# 6_RgbLed.net
KiCad netlist of a schematic drawn in Altium Designer
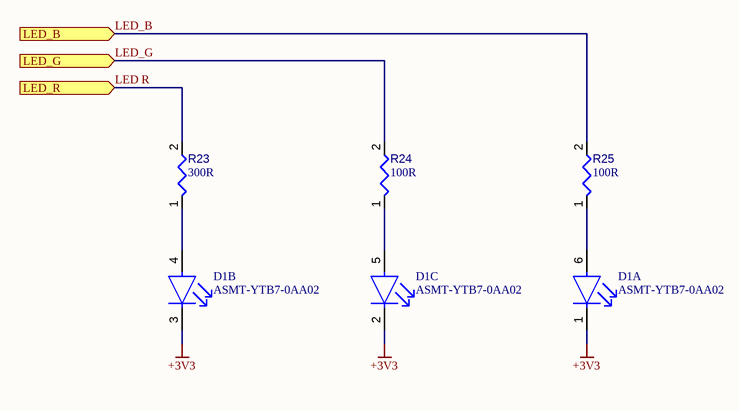
[diagram p0: [6] RgbLed.SchDoc]

(export (version "E")
  (design (tool "Eeschema 10.0.6"))
  (components
    (comp (ref "D1")
      (value "ASMT-YTB7-0AA02")
      (footprint "FP-PLCC-6-MFG")
      (description "LED Tri-Color Blue/Green/Red 469nm/529nm/623nm Chip LED 6-Pin PLCC T/R")
      (libsource (lib "UFCG - Universidade Federal de Campina Grande") (part "0f3d36aaa98356051a15b42400af8f3"))
    )
    (comp (ref "R23")
      (value "300R")
      (footprint "RESC0603(1608)_L")
      (description "Res Thick Film 0603 300 Ohm 5% 1/10W ±200ppm/°C Molded SMD Punched Carrier T/R")
      (fields (field (name "TOLERANCE") "5%") (field (name "Comment") "ERJ-3GEYJ301V"))
      (libsource (lib "UFCG - Universidade Federal de Campina Grande") (part "RES-2"))
    )
    (comp (ref "R24")
      (value "100R")
      (footprint "RESC0603(1608)_L")
      (description "SMD Chip Resistor, 100 Ohm, ï¿½ 1%, 100 mW, 0603 [1608 Metric], Thick Film, Precision")
      (fields (field (name "TOLERANCE") "1%") (field (name "Comment") "ERJ-3EKF1000V"))
      (libsource (lib "UFCG - Universidade Federal de Campina Grande") (part "RES-2"))
    )
    (comp (ref "R25")
      (value "100R")
      (footprint "RESC0603(1608)_L")
      (description "SMD Chip Resistor, 100 Ohm, ï¿½ 1%, 100 mW, 0603 [1608 Metric], Thick Film, Precision")
      (fields (field (name "TOLERANCE") "1%") (field (name "Comment") "ERJ-3EKF1000V"))
      (libsource (lib "UFCG - Universidade Federal de Campina Grande") (part "RES-2"))
    )
  )
  (nets
    (net (code "1") (name "+3V3") (class "Default")
      (node (ref "D1") (pin "1") (pinfunction "Cathode(Blue)_1") (pintype "passive"))
      (node (ref "D1") (pin "2") (pinfunction "Cathode(Green)_2") (pintype "passive"))
      (node (ref "D1") (pin "3") (pinfunction "Cathode(Red)_3") (pintype "passive"))
    )
    (net (code "2") (name "/LED R") (class "Default")
      (node (ref "R23") (pin "2") (pinfunction "2_2") (pintype "passive"))
    )
    (net (code "3") (name "/LED_B") (class "Default")
      (node (ref "R25") (pin "2") (pinfunction "2_2") (pintype "passive"))
    )
    (net (code "4") (name "/LED_G") (class "Default")
      (node (ref "R24") (pin "2") (pinfunction "2_2") (pintype "passive"))
    )
    (net (code "5") (name "Net-(D1A-Anode(Blue))") (class "Default")
      (node (ref "D1") (pin "6") (pinfunction "Anode(Blue)_6") (pintype "passive"))
      (node (ref "R25") (pin "1") (pinfunction "1_1") (pintype "passive"))
    )
    (net (code "6") (name "Net-(D1B-Anode(Red))") (class "Default")
      (node (ref "D1") (pin "4") (pinfunction "Anode(Red)_4") (pintype "passive"))
      (node (ref "R23") (pin "1") (pinfunction "1_1") (pintype "passive"))
    )
    (net (code "7") (name "Net-(D1C-Anode(Green))") (class "Default")
      (node (ref "D1") (pin "5") (pinfunction "Anode(Green)_5") (pintype "passive"))
      (node (ref "R24") (pin "1") (pinfunction "1_1") (pintype "passive"))
    )
  )
)
